# Sheet1.net
KiCad netlist of a schematic drawn in Altium Designer
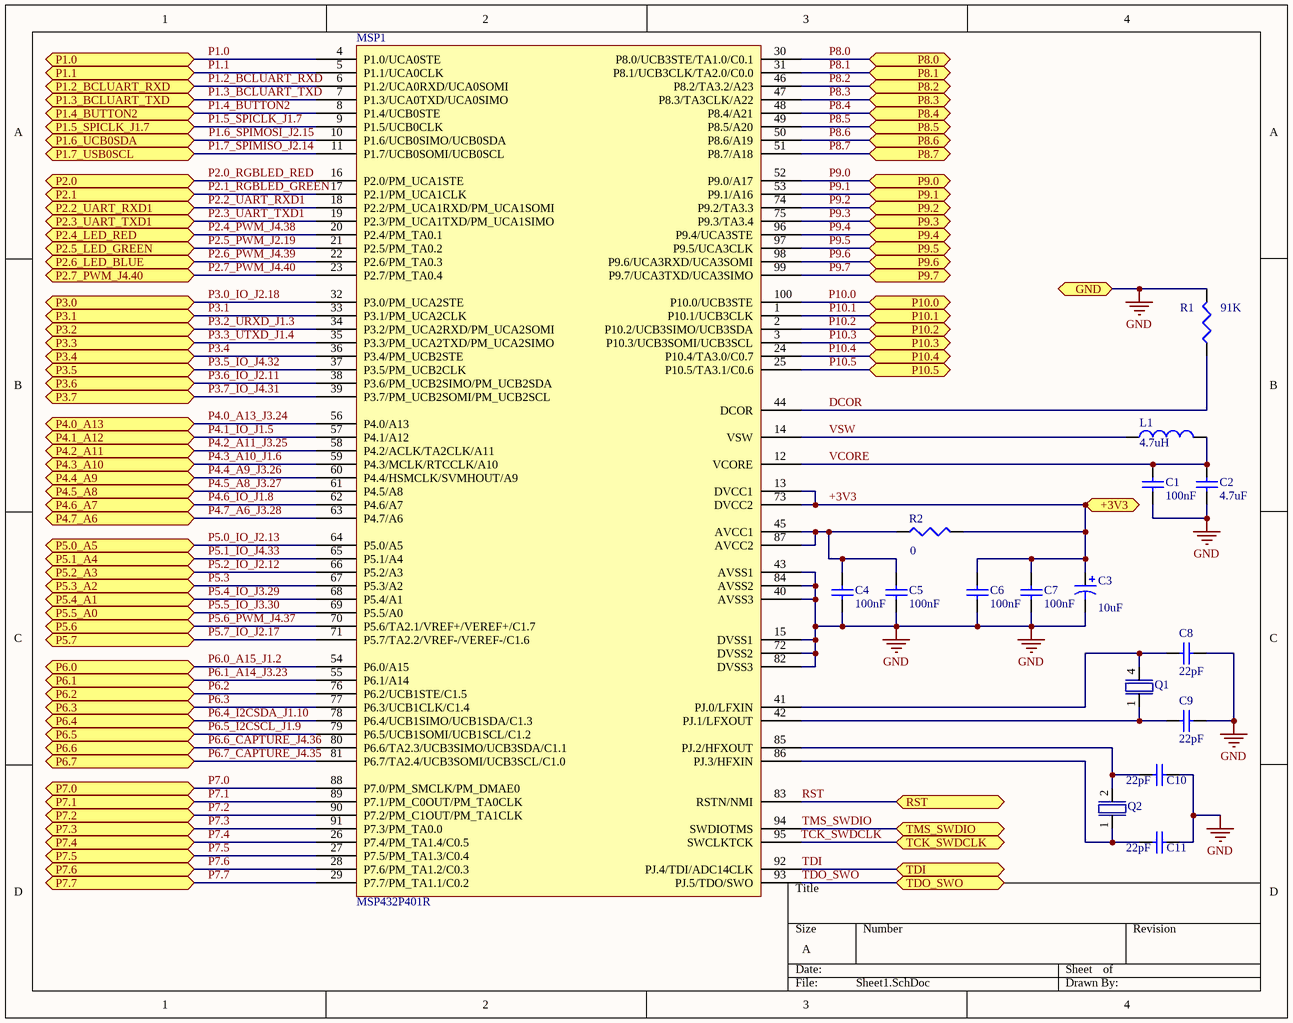
[diagram p0: Sheet1.SchDoc]

(export (version "E")
  (design (tool "Eeschema 10.0.6"))
  (components
    (comp (ref "C1")
      (value "100nF")
      (footprint "0402")
      (description "Capacitor (Semiconductor SIM Model)")
      (fields (field (name "Comment") "Cap Semi") (field (name "PUBLISHER") "Altium Limited"))
      (libsource (lib "Miscellaneous Devices") (part "Cap Semi"))
    )
    (comp (ref "C2")
      (value "4.7uF")
      (footprint "6-0805_L")
      (description "Capacitor (Semiconductor SIM Model)")
      (fields (field (name "Comment") "Cap Semi") (field (name "PUBLISHER") "Altium Limited"))
      (libsource (lib "Miscellaneous Devices") (part "Cap Semi"))
    )
    (comp (ref "C3")
      (value "10uF")
      (footprint "CAPR5-4X5")
      (description "Polarized Capacitor (Surface Mount)")
      (fields (field (name "Comment") "Cap Pol3") (field (name "PUBLISHER") "Altium Limited"))
      (libsource (lib "Miscellaneous Devices") (part "Cap Pol3"))
    )
    (comp (ref "C4")
      (value "100nF")
      (footprint "0402")
      (description "Capacitor (Semiconductor SIM Model)")
      (fields (field (name "Comment") "Cap Semi") (field (name "PUBLISHER") "Altium Limited"))
      (libsource (lib "Miscellaneous Devices") (part "Cap Semi"))
    )
    (comp (ref "C5")
      (value "100nF")
      (footprint "0402")
      (description "Capacitor (Semiconductor SIM Model)")
      (fields (field (name "Comment") "Cap Semi") (field (name "PUBLISHER") "Altium Limited"))
      (libsource (lib "Miscellaneous Devices") (part "Cap Semi"))
    )
    (comp (ref "C6")
      (value "100nF")
      (footprint "0402")
      (description "Capacitor (Semiconductor SIM Model)")
      (fields (field (name "Comment") "Cap Semi") (field (name "PUBLISHER") "Altium Limited"))
      (libsource (lib "Miscellaneous Devices") (part "Cap Semi"))
    )
    (comp (ref "C7")
      (value "100nF")
      (footprint "0402")
      (description "Capacitor (Semiconductor SIM Model)")
      (fields (field (name "Comment") "Cap Semi") (field (name "PUBLISHER") "Altium Limited"))
      (libsource (lib "Miscellaneous Devices") (part "Cap Semi"))
    )
    (comp (ref "C8")
      (value "22pF")
      (footprint "0402")
      (description "Capacitor (Semiconductor SIM Model)")
      (fields (field (name "Comment") "Cap Semi") (field (name "PUBLISHER") "Altium Limited"))
      (libsource (lib "Miscellaneous Devices") (part "Cap Semi"))
    )
    (comp (ref "C9")
      (value "22pF")
      (footprint "0402")
      (description "Capacitor (Semiconductor SIM Model)")
      (fields (field (name "Comment") "Cap Semi") (field (name "PUBLISHER") "Altium Limited"))
      (libsource (lib "Miscellaneous Devices") (part "Cap Semi"))
    )
    (comp (ref "C10")
      (value "22pF")
      (footprint "0402")
      (description "Capacitor (Semiconductor SIM Model)")
      (fields (field (name "Comment") "Cap Semi") (field (name "PUBLISHER") "Altium Limited"))
      (libsource (lib "Miscellaneous Devices") (part "Cap Semi"))
    )
    (comp (ref "C11")
      (value "22pF")
      (footprint "0402")
      (description "Capacitor (Semiconductor SIM Model)")
      (fields (field (name "Comment") "Cap Semi") (field (name "PUBLISHER") "Altium Limited"))
      (libsource (lib "Miscellaneous Devices") (part "Cap Semi"))
    )
    (comp (ref "L1")
      (value "4.7uH")
      (footprint "0806")
      (description "Inductor")
      (fields (field (name "PUBLISHER") "Altium Limited"))
      (libsource (lib "Miscellaneous Devices") (part "Inductor"))
    )
    (comp (ref "MSP1")
      (value "MSP432P401R")
      (footprint "MSP432P401R")
      (libsource (lib "actuatorBoard") (part "MSP432P401R"))
    )
    (comp (ref "Q1")
      (value "Crystal Oscillator")
      (footprint "4-SOJ")
      (libsource (lib "actuatorBoard") (part "Crystal Oscillator"))
    )
    (comp (ref "Q2")
      (value "Crystal Oscillator")
      (footprint "HC-49/US")
      (libsource (lib "") (part "Crystal Oscillator_1"))
    )
    (comp (ref "R1")
      (value "91K")
      (footprint "J1-0603")
      (description "Resistor")
      (fields (field (name "Comment") "Res3") (field (name "PUBLISHER") "Altium Limited"))
      (libsource (lib "Miscellaneous Devices") (part "Res3"))
    )
    (comp (ref "R2")
      (value "0")
      (footprint "J1-0603")
      (description "Resistor")
      (fields (field (name "Comment") "Res3") (field (name "PUBLISHER") "Altium Limited"))
      (libsource (lib "Miscellaneous Devices") (part "Res3"))
    )
  )
  (nets
    (net (code "1") (name "/+3V3") (class "Default")
      (node (ref "C3") (pin "1") (pinfunction "1_1") (pintype "passive"))
      (node (ref "C6") (pin "2") (pinfunction "2_2") (pintype "passive"))
      (node (ref "C7") (pin "2") (pinfunction "2_2") (pintype "passive"))
      (node (ref "MSP1") (pin "13") (pinfunction "DVCC1_13") (pintype "passive"))
      (node (ref "MSP1") (pin "73") (pinfunction "DVCC2_73") (pintype "passive"))
      (node (ref "R2") (pin "2") (pinfunction "2_2") (pintype "passive"))
    )
    (net (code "2") (name "/DCOR") (class "Default")
      (node (ref "MSP1") (pin "44") (pinfunction "DCOR_44") (pintype "passive"))
      (node (ref "R1") (pin "1") (pinfunction "1_1") (pintype "passive"))
    )
    (net (code "3") (name "/P1.0") (class "Default")
      (node (ref "MSP1") (pin "4") (pinfunction "P1.0/UCA0STE_4") (pintype "passive"))
    )
    (net (code "4") (name "/P1.1") (class "Default")
      (node (ref "MSP1") (pin "5") (pinfunction "P1.1/UCA0CLK_5") (pintype "passive"))
    )
    (net (code "5") (name "/P1.2_BCLUART_RXD") (class "Default")
      (node (ref "MSP1") (pin "6") (pinfunction "P1.2/UCA0RXD/UCA0SOMI_6") (pintype "passive"))
    )
    (net (code "6") (name "/P1.3_BCLUART_TXD") (class "Default")
      (node (ref "MSP1") (pin "7") (pinfunction "P1.3/UCA0TXD/UCA0SIMO_7") (pintype "passive"))
    )
    (net (code "7") (name "/P1.4_BUTTON2") (class "Default")
      (node (ref "MSP1") (pin "8") (pinfunction "P1.4/UCB0STE_8") (pintype "passive"))
    )
    (net (code "8") (name "/P1.5_SPICLK_J1.7") (class "Default")
      (node (ref "MSP1") (pin "9") (pinfunction "P1.5/UCB0CLK_9") (pintype "passive"))
    )
    (net (code "9") (name "/P1.6_SPIMOSI_J2.15") (class "Default")
      (node (ref "MSP1") (pin "10") (pinfunction "P1.6/UCB0SIMO/UCB0SDA_10") (pintype "passive"))
    )
    (net (code "10") (name "/P1.7_SPIMISO_J2.14") (class "Default")
      (node (ref "MSP1") (pin "11") (pinfunction "P1.7/UCB0SOMI/UCB0SCL_11") (pintype "passive"))
    )
    (net (code "11") (name "/P2.0_RGBLED_RED") (class "Default")
      (node (ref "MSP1") (pin "16") (pinfunction "P2.0/PM_UCA1STE_16") (pintype "passive"))
    )
    (net (code "12") (name "/P2.1_RGBLED_GREEN") (class "Default")
      (node (ref "MSP1") (pin "17") (pinfunction "P2.1/PM_UCA1CLK_17") (pintype "passive"))
    )
    (net (code "13") (name "/P2.2_UART_RXD1") (class "Default")
      (node (ref "MSP1") (pin "18") (pinfunction "P2.2/PM_UCA1RXD/PM_UCA1SOMI_18") (pintype "passive"))
    )
    (net (code "14") (name "/P2.3_UART_TXD1") (class "Default")
      (node (ref "MSP1") (pin "19") (pinfunction "P2.3/PM_UCA1TXD/PM_UCA1SIMO_19") (pintype "passive"))
    )
    (net (code "15") (name "/P2.4_PWM_J4.38") (class "Default")
      (node (ref "MSP1") (pin "20") (pinfunction "P2.4/PM_TA0.1_20") (pintype "passive"))
    )
    (net (code "16") (name "/P2.5_PWM_J2.19") (class "Default")
      (node (ref "MSP1") (pin "21") (pinfunction "P2.5/PM_TA0.2_21") (pintype "passive"))
    )
    (net (code "17") (name "/P2.6_PWM_J4.39") (class "Default")
      (node (ref "MSP1") (pin "22") (pinfunction "P2.6/PM_TA0.3_22") (pintype "passive"))
    )
    (net (code "18") (name "/P2.7_PWM_J4.40") (class "Default")
      (node (ref "MSP1") (pin "23") (pinfunction "P2.7/PM_TA0.4_23") (pintype "passive"))
    )
    (net (code "19") (name "/P3.0_IO_J2.18") (class "Default")
      (node (ref "MSP1") (pin "32") (pinfunction "P3.0/PM_UCA2STE_32") (pintype "passive"))
    )
    (net (code "20") (name "/P3.1") (class "Default")
      (node (ref "MSP1") (pin "33") (pinfunction "P3.1/PM_UCA2CLK_33") (pintype "passive"))
    )
    (net (code "21") (name "/P3.2_URXD_J1.3") (class "Default")
      (node (ref "MSP1") (pin "34") (pinfunction "P3.2/PM_UCA2RXD/PM_UCA2SOMI_34") (pintype "passive"))
    )
    (net (code "22") (name "/P3.3_UTXD_J1.4") (class "Default")
      (node (ref "MSP1") (pin "35") (pinfunction "P3.3/PM_UCA2TXD/PM_UCA2SIMO_35") (pintype "passive"))
    )
    (net (code "23") (name "/P3.4") (class "Default")
      (node (ref "MSP1") (pin "36") (pinfunction "P3.4/PM_UCB2STE_36") (pintype "passive"))
    )
    (net (code "24") (name "/P3.5_IO_J4.32") (class "Default")
      (node (ref "MSP1") (pin "37") (pinfunction "P3.5/PM_UCB2CLK_37") (pintype "passive"))
    )
    (net (code "25") (name "/P3.6_IO_J2.11") (class "Default")
      (node (ref "MSP1") (pin "38") (pinfunction "P3.6/PM_UCB2SIMO/PM_UCB2SDA_38") (pintype "passive"))
    )
    (net (code "26") (name "/P3.7_IO_J4.31") (class "Default")
      (node (ref "MSP1") (pin "39") (pinfunction "P3.7/PM_UCB2SOMI/PM_UCB2SCL_39") (pintype "passive"))
    )
    (net (code "27") (name "/P4.0_A13_J3.24") (class "Default")
      (node (ref "MSP1") (pin "56") (pinfunction "P4.0/A13_56") (pintype "passive"))
    )
    (net (code "28") (name "/P4.1_IO_J1.5") (class "Default")
      (node (ref "MSP1") (pin "57") (pinfunction "P4.1/A12_57") (pintype "passive"))
    )
    (net (code "29") (name "/P4.2_A11_J3.25") (class "Default")
      (node (ref "MSP1") (pin "58") (pinfunction "P4.2/ACLK/TA2CLK/A11_58") (pintype "passive"))
    )
    (net (code "30") (name "/P4.3_A10_J1.6") (class "Default")
      (node (ref "MSP1") (pin "59") (pinfunction "P4.3/MCLK/RTCCLK/A10_59") (pintype "passive"))
    )
    (net (code "31") (name "/P4.4_A9_J3.26") (class "Default")
      (node (ref "MSP1") (pin "60") (pinfunction "P4.4/HSMCLK/SVMHOUT/A9_60") (pintype "passive"))
    )
    (net (code "32") (name "/P4.5_A8_J3.27") (class "Default")
      (node (ref "MSP1") (pin "61") (pinfunction "P4.5/A8_61") (pintype "passive"))
    )
    (net (code "33") (name "/P4.6_IO_J1.8") (class "Default")
      (node (ref "MSP1") (pin "62") (pinfunction "P4.6/A7_62") (pintype "passive"))
    )
    (net (code "34") (name "/P4.7_A6_J3.28") (class "Default")
      (node (ref "MSP1") (pin "63") (pinfunction "P4.7/A6_63") (pintype "passive"))
    )
    (net (code "35") (name "/P5.0_IO_J2.13") (class "Default")
      (node (ref "MSP1") (pin "64") (pinfunction "P5.0/A5_64") (pintype "passive"))
    )
    (net (code "36") (name "/P5.1_IO_J4.33") (class "Default")
      (node (ref "MSP1") (pin "65") (pinfunction "P5.1/A4_65") (pintype "passive"))
    )
    (net (code "37") (name "/P5.2_IO_J2.12") (class "Default")
      (node (ref "MSP1") (pin "66") (pinfunction "P5.2/A3_66") (pintype "passive"))
    )
    (net (code "38") (name "/P5.3") (class "Default")
      (node (ref "MSP1") (pin "67") (pinfunction "P5.3/A2_67") (pintype "passive"))
    )
    (net (code "39") (name "/P5.4_IO_J3.29") (class "Default")
      (node (ref "MSP1") (pin "68") (pinfunction "P5.4/A1_68") (pintype "passive"))
    )
    (net (code "40") (name "/P5.5_IO_J3.30") (class "Default")
      (node (ref "MSP1") (pin "69") (pinfunction "P5.5/A0_69") (pintype "passive"))
    )
    (net (code "41") (name "/P5.6_PWM_J4.37") (class "Default")
      (node (ref "MSP1") (pin "70") (pinfunction "P5.6/TA2.1/VREF+/VEREF+/C1.7_70") (pintype "passive"))
    )
    (net (code "42") (name "/P5.7_IO_J2.17") (class "Default")
      (node (ref "MSP1") (pin "71") (pinfunction "P5.7/TA2.2/VREF-/VEREF-/C1.6_71") (pintype "passive"))
    )
    (net (code "43") (name "/P6.0_A15_J1.2") (class "Default")
      (node (ref "MSP1") (pin "54") (pinfunction "P6.0/A15_54") (pintype "passive"))
    )
    (net (code "44") (name "/P6.1_A14_J3.23") (class "Default")
      (node (ref "MSP1") (pin "55") (pinfunction "P6.1/A14_55") (pintype "passive"))
    )
    (net (code "45") (name "/P6.2") (class "Default")
      (node (ref "MSP1") (pin "76") (pinfunction "P6.2/UCB1STE/C1.5_76") (pintype "passive"))
    )
    (net (code "46") (name "/P6.3") (class "Default")
      (node (ref "MSP1") (pin "77") (pinfunction "P6.3/UCB1CLK/C1.4_77") (pintype "passive"))
    )
    (net (code "47") (name "/P6.4_I2CSDA_J1.10") (class "Default")
      (node (ref "MSP1") (pin "78") (pinfunction "P6.4/UCB1SIMO/UCB1SDA/C1.3_78") (pintype "passive"))
    )
    (net (code "48") (name "/P6.5_I2CSCL_J1.9") (class "Default")
      (node (ref "MSP1") (pin "79") (pinfunction "P6.5/UCB1SOMI/UCB1SCL/C1.2_79") (pintype "passive"))
    )
    (net (code "49") (name "/P6.6_CAPTURE_J4.36") (class "Default")
      (node (ref "MSP1") (pin "80") (pinfunction "P6.6/TA2.3/UCB3SIMO/UCB3SDA/C1.1_80") (pintype "passive"))
    )
    (net (code "50") (name "/P6.7_CAPTURE_J4.35") (class "Default")
      (node (ref "MSP1") (pin "81") (pinfunction "P6.7/TA2.4/UCB3SOMI/UCB3SCL/C1.0_81") (pintype "passive"))
    )
    (net (code "51") (name "/P7.0") (class "Default")
      (node (ref "MSP1") (pin "88") (pinfunction "P7.0/PM_SMCLK/PM_DMAE0_88") (pintype "passive"))
    )
    (net (code "52") (name "/P7.1") (class "Default")
      (node (ref "MSP1") (pin "89") (pinfunction "P7.1/PM_C0OUT/PM_TA0CLK_89") (pintype "passive"))
    )
    (net (code "53") (name "/P7.2") (class "Default")
      (node (ref "MSP1") (pin "90") (pinfunction "P7.2/PM_C1OUT/PM_TA1CLK_90") (pintype "passive"))
    )
    (net (code "54") (name "/P7.3") (class "Default")
      (node (ref "MSP1") (pin "91") (pinfunction "P7.3/PM_TA0.0_91") (pintype "passive"))
    )
    (net (code "55") (name "/P7.4") (class "Default")
      (node (ref "MSP1") (pin "26") (pinfunction "P7.4/PM_TA1.4/C0.5_26") (pintype "passive"))
    )
    (net (code "56") (name "/P7.5") (class "Default")
      (node (ref "MSP1") (pin "27") (pinfunction "P7.5/PM_TA1.3/C0.4_27") (pintype "passive"))
    )
    (net (code "57") (name "/P7.6") (class "Default")
      (node (ref "MSP1") (pin "28") (pinfunction "P7.6/PM_TA1.2/C0.3_28") (pintype "passive"))
    )
    (net (code "58") (name "/P7.7") (class "Default")
      (node (ref "MSP1") (pin "29") (pinfunction "P7.7/PM_TA1.1/C0.2_29") (pintype "passive"))
    )
    (net (code "59") (name "/P8.0") (class "Default")
      (node (ref "MSP1") (pin "30") (pinfunction "P8.0/UCB3STE/TA1.0/C0.1_30") (pintype "passive"))
    )
    (net (code "60") (name "/P8.1") (class "Default")
      (node (ref "MSP1") (pin "31") (pinfunction "P8.1/UCB3CLK/TA2.0/C0.0_31") (pintype "passive"))
    )
    (net (code "61") (name "/P8.2") (class "Default")
      (node (ref "MSP1") (pin "46") (pinfunction "P8.2/TA3.2/A23_46") (pintype "passive"))
    )
    (net (code "62") (name "/P8.3") (class "Default")
      (node (ref "MSP1") (pin "47") (pinfunction "P8.3/TA3CLK/A22_47") (pintype "passive"))
    )
    (net (code "63") (name "/P8.4") (class "Default")
      (node (ref "MSP1") (pin "48") (pinfunction "P8.4/A21_48") (pintype "passive"))
    )
    (net (code "64") (name "/P8.5") (class "Default")
      (node (ref "MSP1") (pin "49") (pinfunction "P8.5/A20_49") (pintype "passive"))
    )
    (net (code "65") (name "/P8.6") (class "Default")
      (node (ref "MSP1") (pin "50") (pinfunction "P8.6/A19_50") (pintype "passive"))
    )
    (net (code "66") (name "/P8.7") (class "Default")
      (node (ref "MSP1") (pin "51") (pinfunction "P8.7/A18_51") (pintype "passive"))
    )
    (net (code "67") (name "/P9.0") (class "Default")
      (node (ref "MSP1") (pin "52") (pinfunction "P9.0/A17_52") (pintype "passive"))
    )
    (net (code "68") (name "/P9.1") (class "Default")
      (node (ref "MSP1") (pin "53") (pinfunction "P9.1/A16_53") (pintype "passive"))
    )
    (net (code "69") (name "/P9.2") (class "Default")
      (node (ref "MSP1") (pin "74") (pinfunction "P9.2/TA3.3_74") (pintype "passive"))
    )
    (net (code "70") (name "/P9.3") (class "Default")
      (node (ref "MSP1") (pin "75") (pinfunction "P9.3/TA3.4_75") (pintype "passive"))
    )
    (net (code "71") (name "/P9.4") (class "Default")
      (node (ref "MSP1") (pin "96") (pinfunction "P9.4/UCA3STE_96") (pintype "passive"))
    )
    (net (code "72") (name "/P9.5") (class "Default")
      (node (ref "MSP1") (pin "97") (pinfunction "P9.5/UCA3CLK_97") (pintype "passive"))
    )
    (net (code "73") (name "/P9.6") (class "Default")
      (node (ref "MSP1") (pin "98") (pinfunction "P9.6/UCA3RXD/UCA3SOMI_98") (pintype "passive"))
    )
    (net (code "74") (name "/P9.7") (class "Default")
      (node (ref "MSP1") (pin "99") (pinfunction "P9.7/UCA3TXD/UCA3SIMO_99") (pintype "passive"))
    )
    (net (code "75") (name "/P10.0") (class "Default")
      (node (ref "MSP1") (pin "100") (pinfunction "P10.0/UCB3STE_100") (pintype "passive"))
    )
    (net (code "76") (name "/P10.1") (class "Default")
      (node (ref "MSP1") (pin "1") (pinfunction "P10.1/UCB3CLK_1") (pintype "passive"))
    )
    (net (code "77") (name "/P10.2") (class "Default")
      (node (ref "MSP1") (pin "2") (pinfunction "P10.2/UCB3SIMO/UCB3SDA_2") (pintype "passive"))
    )
    (net (code "78") (name "/P10.3") (class "Default")
      (node (ref "MSP1") (pin "3") (pinfunction "P10.3/UCB3SOMI/UCB3SCL_3") (pintype "passive"))
    )
    (net (code "79") (name "/P10.4") (class "Default")
      (node (ref "MSP1") (pin "24") (pinfunction "P10.4/TA3.0/C0.7_24") (pintype "passive"))
    )
    (net (code "80") (name "/P10.5") (class "Default")
      (node (ref "MSP1") (pin "25") (pinfunction "P10.5/TA3.1/C0.6_25") (pintype "passive"))
    )
    (net (code "81") (name "/RST") (class "Default")
      (node (ref "MSP1") (pin "83") (pinfunction "RSTN/NMI_83") (pintype "passive"))
    )
    (net (code "82") (name "/TCK_SWDCLK") (class "Default")
      (node (ref "MSP1") (pin "95") (pinfunction "SWCLKTCK_95") (pintype "passive"))
    )
    (net (code "83") (name "/TDI") (class "Default")
      (node (ref "MSP1") (pin "92") (pinfunction "PJ.4/TDI/ADC14CLK_92") (pintype "passive"))
    )
    (net (code "84") (name "/TDO_SWO") (class "Default")
      (node (ref "MSP1") (pin "93") (pinfunction "PJ.5/TDO/SWO_93") (pintype "passive"))
    )
    (net (code "85") (name "/TMS_SWDIO") (class "Default")
      (node (ref "MSP1") (pin "94") (pinfunction "SWDIOTMS_94") (pintype "passive"))
    )
    (net (code "86") (name "/VCORE") (class "Default")
      (node (ref "C1") (pin "2") (pinfunction "2_2") (pintype "passive"))
      (node (ref "C2") (pin "2") (pinfunction "2_2") (pintype "passive"))
      (node (ref "L1") (pin "2") (pinfunction "2_2") (pintype "passive"))
      (node (ref "MSP1") (pin "12") (pinfunction "VCORE_12") (pintype "passive"))
    )
    (net (code "87") (name "/VSW") (class "Default")
      (node (ref "L1") (pin "1") (pinfunction "1_1") (pintype "passive"))
      (node (ref "MSP1") (pin "14") (pinfunction "VSW_14") (pintype "passive"))
    )
    (net (code "88") (name "GND") (class "Default")
      (node (ref "C1") (pin "1") (pinfunction "1_1") (pintype "passive"))
      (node (ref "C10") (pin "1") (pinfunction "1_1") (pintype "passive"))
      (node (ref "C11") (pin "1") (pinfunction "1_1") (pintype "passive"))
      (node (ref "C2") (pin "1") (pinfunction "1_1") (pintype "passive"))
      (node (ref "C3") (pin "2") (pinfunction "2_2") (pintype "passive"))
      (node (ref "C4") (pin "1") (pinfunction "1_1") (pintype "passive"))
      (node (ref "C5") (pin "1") (pinfunction "1_1") (pintype "passive"))
      (node (ref "C6") (pin "1") (pinfunction "1_1") (pintype "passive"))
      (node (ref "C7") (pin "1") (pinfunction "1_1") (pintype "passive"))
      (node (ref "C8") (pin "1") (pinfunction "1_1") (pintype "passive"))
      (node (ref "C9") (pin "1") (pinfunction "1_1") (pintype "passive"))
      (node (ref "MSP1") (pin "15") (pinfunction "DVSS1_15") (pintype "passive"))
      (node (ref "MSP1") (pin "40") (pinfunction "AVSS3_40") (pintype "passive"))
      (node (ref "MSP1") (pin "43") (pinfunction "AVSS1_43") (pintype "passive"))
      (node (ref "MSP1") (pin "72") (pinfunction "DVSS2_72") (pintype "passive"))
      (node (ref "MSP1") (pin "82") (pinfunction "DVSS3_82") (pintype "passive"))
      (node (ref "MSP1") (pin "84") (pinfunction "AVSS2_84") (pintype "passive"))
      (node (ref "R1") (pin "2") (pinfunction "2_2") (pintype "passive"))
    )
    (net (code "89") (name "Net-(MSP1-AVCC1)") (class "Default")
      (node (ref "C4") (pin "2") (pinfunction "2_2") (pintype "passive"))
      (node (ref "C5") (pin "2") (pinfunction "2_2") (pintype "passive"))
      (node (ref "MSP1") (pin "45") (pinfunction "AVCC1_45") (pintype "passive"))
      (node (ref "MSP1") (pin "87") (pinfunction "AVCC2_87") (pintype "passive"))
      (node (ref "R2") (pin "1") (pinfunction "1_1") (pintype "passive"))
    )
    (net (code "90") (name "Net-(MSP1-PJ.0{slash}LFXIN)") (class "Default")
      (node (ref "C8") (pin "2") (pinfunction "2_2") (pintype "passive"))
      (node (ref "MSP1") (pin "41") (pinfunction "PJ.0/LFXIN_41") (pintype "passive"))
      (node (ref "Q1") (pin "4") (pinfunction "4_4") (pintype "passive"))
    )
    (net (code "91") (name "Net-(MSP1-PJ.1{slash}LFXOUT)") (class "Default")
      (node (ref "C9") (pin "2") (pinfunction "2_2") (pintype "passive"))
      (node (ref "MSP1") (pin "42") (pinfunction "PJ.1/LFXOUT_42") (pintype "passive"))
      (node (ref "Q1") (pin "1") (pinfunction "1_1") (pintype "passive"))
    )
    (net (code "92") (name "Net-(MSP1-PJ.2{slash}HFXOUT)") (class "Default")
      (node (ref "C10") (pin "2") (pinfunction "2_2") (pintype "passive"))
      (node (ref "MSP1") (pin "85") (pinfunction "PJ.2/HFXOUT_85") (pintype "passive"))
      (node (ref "Q2") (pin "2") (pinfunction "2_2") (pintype "passive"))
    )
    (net (code "93") (name "Net-(MSP1-PJ.3{slash}HFXIN)") (class "Default")
      (node (ref "C11") (pin "2") (pinfunction "2_2") (pintype "passive"))
      (node (ref "MSP1") (pin "86") (pinfunction "PJ.3/HFXIN_86") (pintype "passive"))
      (node (ref "Q2") (pin "1") (pinfunction "1_1") (pintype "passive"))
    )
  )
)
